# Minimal_carrier_board_for_CM4_rev_E.net
KiCad netlist of a schematic drawn in EAGLE
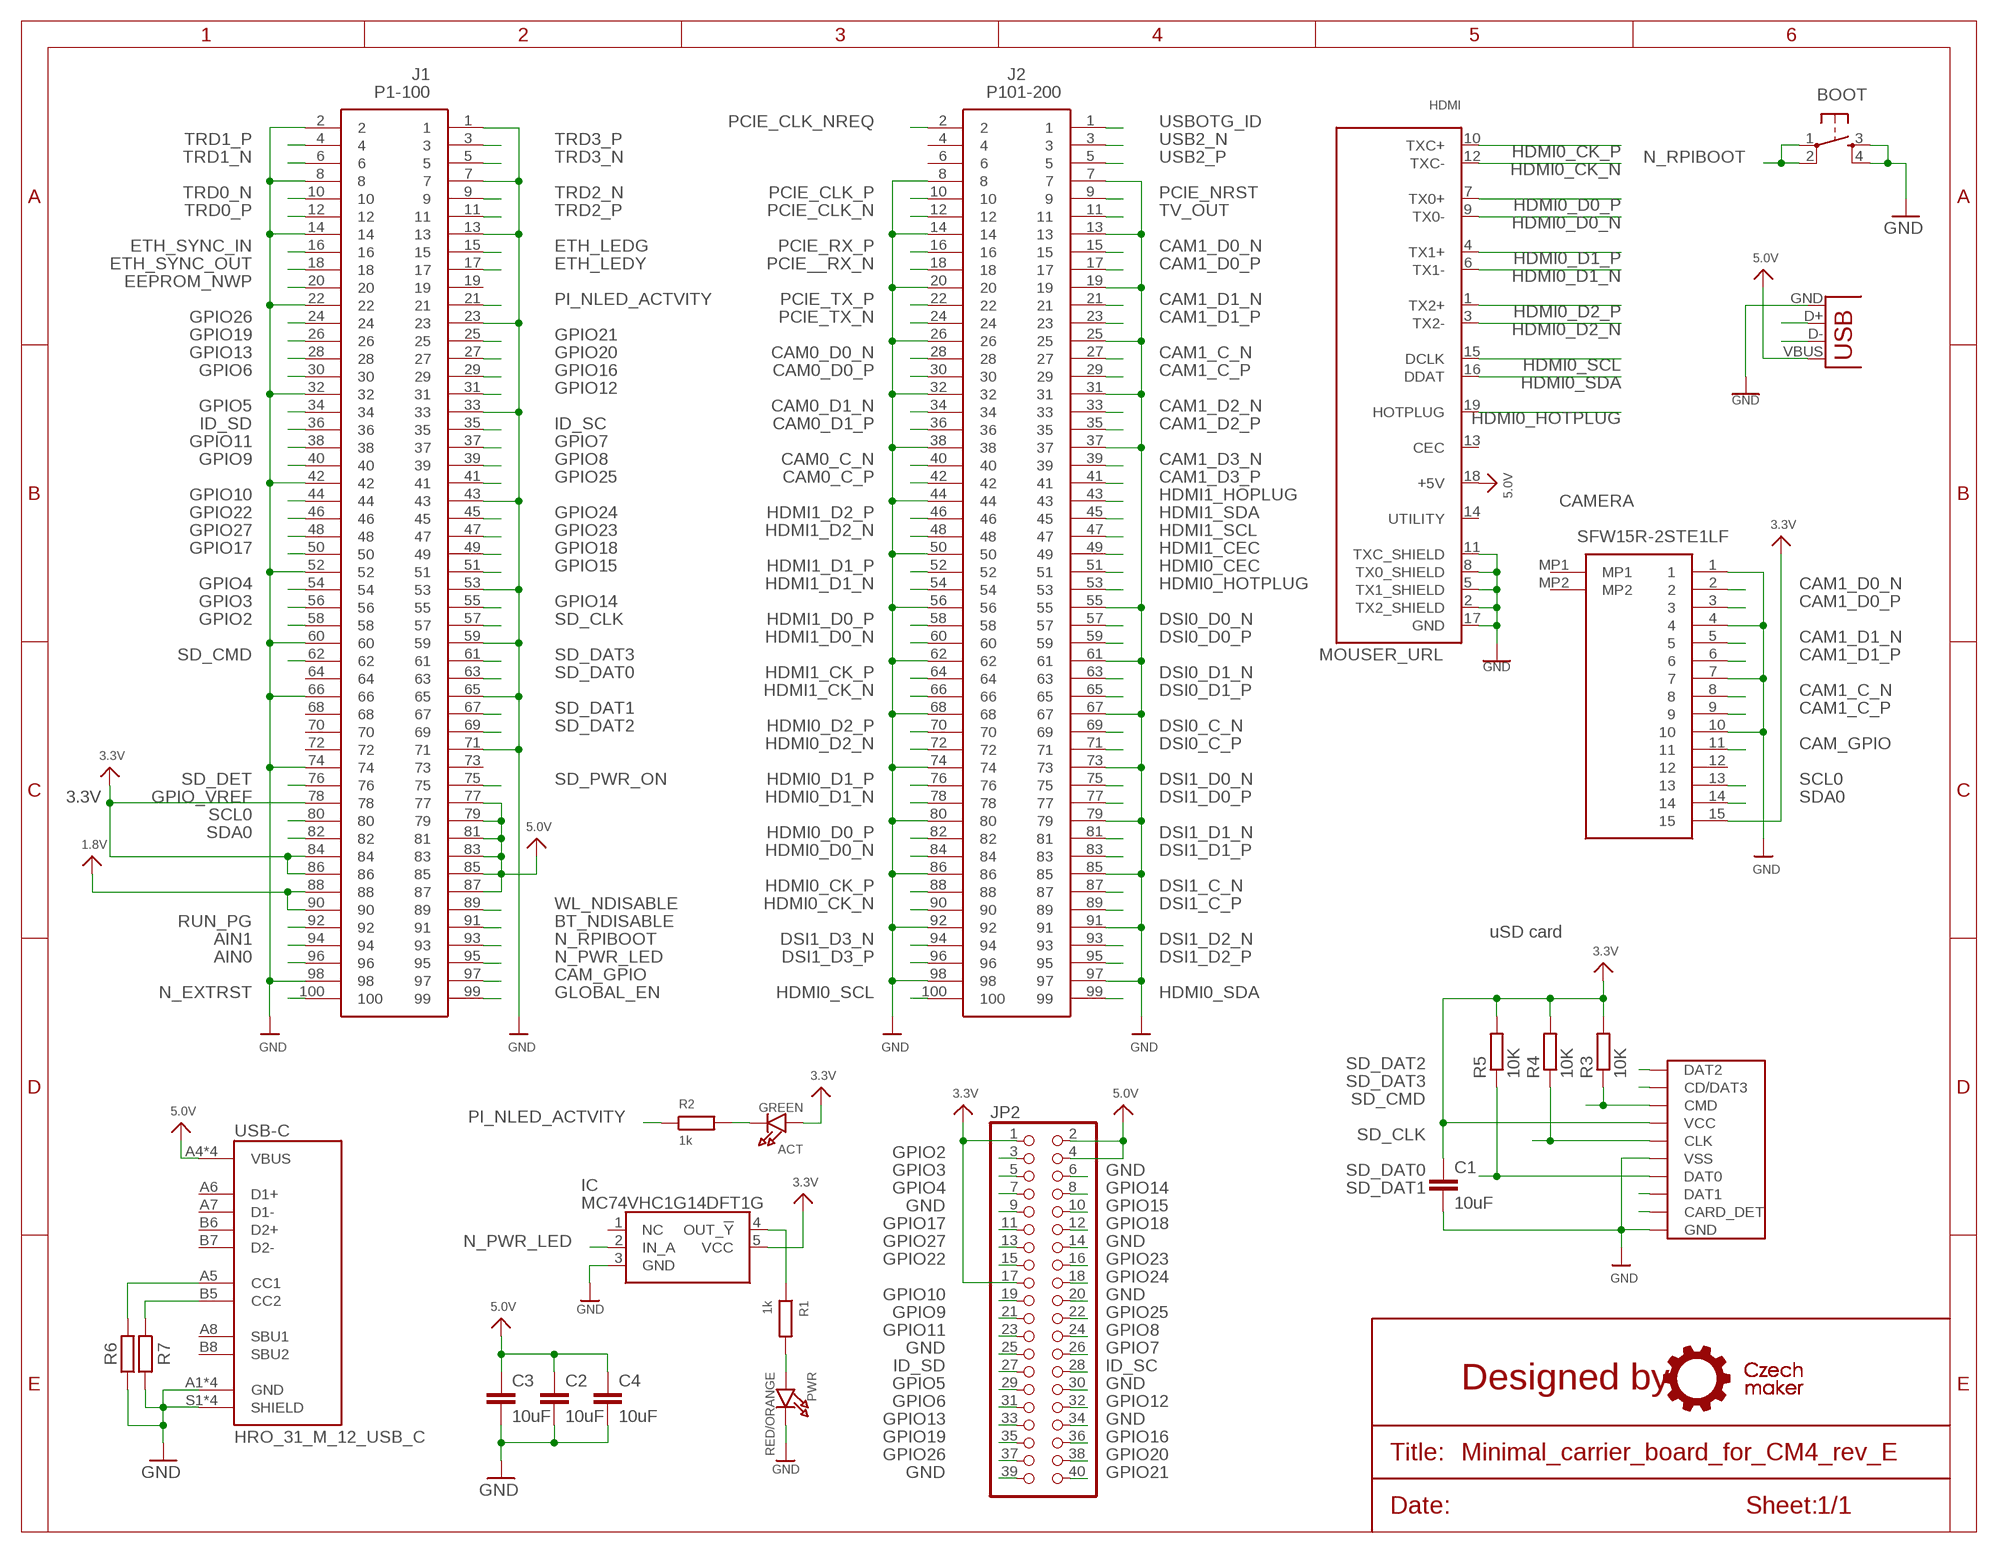
[diagram p0: schematic, sheet 1]

(export (version "E")
  (design (tool "Eeschema 10.0.6"))
  (components
    (comp (ref "ACT")
      (value "GREEN")
      (footprint "eagle-import:CHIPLED_0805_NOOUTLINE")
      (libsource (lib "eagle-import") (part "LED0805_NOOUTLINE"))
    )
    (comp (ref "BOOT")
      (value "TACTILE_SWITCHE_5X5_MICRO_")
      (footprint "eagle-import:TACTILE_SWITCH_5X5_MICRO")
      (libsource (lib "eagle-import") (part "TACTILE_SWITCHE_5X5_MICRO_"))
    )
    (comp (ref "C1")
      (value "10uF")
      (footprint "eagle-import:C0805")
      (libsource (lib "eagle-import") (part "C-EUC0805"))
    )
    (comp (ref "C2")
      (value "10uF")
      (footprint "eagle-import:C0805")
      (libsource (lib "eagle-import") (part "C-EUC0805"))
    )
    (comp (ref "C3")
      (value "10uF")
      (footprint "eagle-import:C0805")
      (libsource (lib "eagle-import") (part "C-EUC0805"))
    )
    (comp (ref "C4")
      (value "10uF")
      (footprint "eagle-import:C0805")
      (libsource (lib "eagle-import") (part "C-EUC0805"))
    )
    (comp (ref "CAMERA")
      (value "SFW15R-2STE1LF")
      (footprint "eagle-import:SFW15R2STE1LF")
      (fields (field (name "MOUSER_PART_NUMBER") "649-SFW15R-2STE1LF"))
      (libsource (lib "eagle-import") (part "SFW15R-2STE1LF"))
    )
    (comp (ref "HDMI")
      (value "HDMI_MOLEX_47151-0001")
      (footprint "eagle-import:HDMI_MOLEX_47151-0001")
      (libsource (lib "eagle-import") (part "HDMI_MOLEX_47151-0001"))
    )
    (comp (ref "IC")
      (value "MC74VHC1G14DFT1G")
      (footprint "eagle-import:SOT65P210X110-5N")
      (fields (field (name "MOUSER_PART_NUMBER") "863-MC74VHC1G14DFT1G"))
      (libsource (lib "eagle-import") (part "MC74VHC1G14DFT1G"))
    )
    (comp (ref "J1")
      (value "P1-100")
      (footprint "eagle-import:DF40C100DS04V51")
      (fields
        (field (name "MANUFACTURER_PART_NUMBER") "DF40C-100DS-0.4V(51)")
        (field (name "MOUSER_PART_NUMBER") "798-DF40C100DS0.4V51")
      )
      (libsource (lib "eagle-import") (part "DF40C-100DS-0.4V_51_"))
    )
    (comp (ref "J2")
      (value "P101-200")
      (footprint "eagle-import:DF40C100DS04V51")
      (fields
        (field (name "MANUFACTURER_PART_NUMBER") "DF40C-100DS-0.4V(51)")
        (field (name "MOUSER_PART_NUMBER") "798-DF40C100DS0.4V51")
      )
      (libsource (lib "eagle-import") (part "DF40C-100DS-0.4V_51_"))
    )
    (comp (ref "JP2")
      (value "PINHD-2X20")
      (footprint "eagle-import:2X20")
      (libsource (lib "eagle-import") (part "PINHD-2X20"))
    )
    (comp (ref "PWR")
      (value "RED/ORANGE")
      (footprint "eagle-import:CHIPLED_0805_NOOUTLINE")
      (libsource (lib "eagle-import") (part "LED0805_NOOUTLINE"))
    )
    (comp (ref "R1")
      (value "1k")
      (footprint "eagle-import:R0805")
      (libsource (lib "eagle-import") (part "R-EU_R0805"))
    )
    (comp (ref "R2")
      (value "1k")
      (footprint "eagle-import:R0805")
      (libsource (lib "eagle-import") (part "R-EU_R0805"))
    )
    (comp (ref "R3")
      (value "10K")
      (footprint "eagle-import:R0805")
      (libsource (lib "eagle-import") (part "R-EU_R0805"))
    )
    (comp (ref "R4")
      (value "10K")
      (footprint "eagle-import:R0805")
      (libsource (lib "eagle-import") (part "R-EU_R0805"))
    )
    (comp (ref "R5")
      (value "10K")
      (footprint "eagle-import:R0805")
      (libsource (lib "eagle-import") (part "R-EU_R0805"))
    )
    (comp (ref "R6")
      (value "5.1k")
      (footprint "eagle-import:R0805")
      (libsource (lib "eagle-import") (part "R-EU_R0805"))
    )
    (comp (ref "R7")
      (value "5.1k")
      (footprint "eagle-import:R0805")
      (libsource (lib "eagle-import") (part "R-EU_R0805"))
    )
    (comp (ref "SD_CARD")
      (value "MICRO_SD_CARD_")
      (footprint "eagle-import:TFP09-2--12B")
      (libsource (lib "eagle-import") (part "MICRO_SD_CARD_"))
    )
    (comp (ref "USB-A")
      (value "USBA-PTH")
      (footprint "eagle-import:USB-A-F-PTH")
      (libsource (lib "eagle-import") (part "USBA-PTH"))
    )
    (comp (ref "USB-C")
      (value "HRO_31_M_12_USB_C")
      (footprint "eagle-import:HRO_31_M_12_USB_C")
      (libsource (lib "eagle-import") (part "HRO_31_M_12_USB_C"))
    )
  )
  (nets
    (net (code "1") (name "/AIN0") (class "Default")
      (node (ref "J1") (pin "96") (pinfunction "96_96") (pintype "bidirectional"))
    )
    (net (code "2") (name "/AIN1") (class "Default")
      (node (ref "J1") (pin "94") (pinfunction "94_94") (pintype "bidirectional"))
    )
    (net (code "3") (name "/BT_NDISABLE") (class "Default")
      (node (ref "J1") (pin "91") (pinfunction "91_91") (pintype "bidirectional"))
    )
    (net (code "4") (name "/CAM0_C_N") (class "Default")
      (node (ref "J2") (pin "40") (pinfunction "40_40") (pintype "bidirectional"))
    )
    (net (code "5") (name "/CAM0_C_P") (class "Default")
      (node (ref "J2") (pin "42") (pinfunction "42_42") (pintype "bidirectional"))
    )
    (net (code "6") (name "/CAM0_D0_N") (class "Default")
      (node (ref "J2") (pin "28") (pinfunction "28_28") (pintype "bidirectional"))
    )
    (net (code "7") (name "/CAM0_D0_P") (class "Default")
      (node (ref "J2") (pin "30") (pinfunction "30_30") (pintype "bidirectional"))
    )
    (net (code "8") (name "/CAM0_D1_N") (class "Default")
      (node (ref "J2") (pin "34") (pinfunction "34_34") (pintype "bidirectional"))
    )
    (net (code "9") (name "/CAM0_D1_P") (class "Default")
      (node (ref "J2") (pin "36") (pinfunction "36_36") (pintype "bidirectional"))
    )
    (net (code "10") (name "/CAM1_C_N") (class "Default")
      (node (ref "CAMERA") (pin "8") (pinfunction "8_8") (pintype "bidirectional"))
      (node (ref "J2") (pin "27") (pinfunction "27_27") (pintype "bidirectional"))
    )
    (net (code "11") (name "/CAM1_C_P") (class "Default")
      (node (ref "CAMERA") (pin "9") (pinfunction "9_9") (pintype "bidirectional"))
      (node (ref "J2") (pin "29") (pinfunction "29_29") (pintype "bidirectional"))
    )
    (net (code "12") (name "/CAM1_D0_N") (class "Default")
      (node (ref "CAMERA") (pin "2") (pinfunction "2_2") (pintype "bidirectional"))
      (node (ref "J2") (pin "15") (pinfunction "15_15") (pintype "bidirectional"))
    )
    (net (code "13") (name "/CAM1_D0_P") (class "Default")
      (node (ref "CAMERA") (pin "3") (pinfunction "3_3") (pintype "bidirectional"))
      (node (ref "J2") (pin "17") (pinfunction "17_17") (pintype "bidirectional"))
    )
    (net (code "14") (name "/CAM1_D1_N") (class "Default")
      (node (ref "CAMERA") (pin "5") (pinfunction "5_5") (pintype "bidirectional"))
      (node (ref "J2") (pin "21") (pinfunction "21_21") (pintype "bidirectional"))
    )
    (net (code "15") (name "/CAM1_D1_P") (class "Default")
      (node (ref "CAMERA") (pin "6") (pinfunction "6_6") (pintype "bidirectional"))
      (node (ref "J2") (pin "23") (pinfunction "23_23") (pintype "bidirectional"))
    )
    (net (code "16") (name "/CAM1_D2_N") (class "Default")
      (node (ref "J2") (pin "33") (pinfunction "33_33") (pintype "bidirectional"))
    )
    (net (code "17") (name "/CAM1_D2_P") (class "Default")
      (node (ref "J2") (pin "35") (pinfunction "35_35") (pintype "bidirectional"))
    )
    (net (code "18") (name "/CAM1_D3_N") (class "Default")
      (node (ref "J2") (pin "39") (pinfunction "39_39") (pintype "bidirectional"))
    )
    (net (code "19") (name "/CAM1_D3_P") (class "Default")
      (node (ref "J2") (pin "41") (pinfunction "41_41") (pintype "bidirectional"))
    )
    (net (code "20") (name "/CAM_GPIO") (class "Default")
      (node (ref "CAMERA") (pin "11") (pinfunction "11_11") (pintype "bidirectional"))
      (node (ref "J1") (pin "97") (pinfunction "97_97") (pintype "bidirectional"))
    )
    (net (code "21") (name "/DSI0_C_N") (class "Default")
      (node (ref "J2") (pin "69") (pinfunction "69_69") (pintype "bidirectional"))
    )
    (net (code "22") (name "/DSI0_C_P") (class "Default")
      (node (ref "J2") (pin "71") (pinfunction "71_71") (pintype "bidirectional"))
    )
    (net (code "23") (name "/DSI0_D0_N") (class "Default")
      (node (ref "J2") (pin "57") (pinfunction "57_57") (pintype "bidirectional"))
    )
    (net (code "24") (name "/DSI0_D0_P") (class "Default")
      (node (ref "J2") (pin "59") (pinfunction "59_59") (pintype "bidirectional"))
    )
    (net (code "25") (name "/DSI0_D1_N") (class "Default")
      (node (ref "J2") (pin "63") (pinfunction "63_63") (pintype "bidirectional"))
    )
    (net (code "26") (name "/DSI0_D1_P") (class "Default")
      (node (ref "J2") (pin "65") (pinfunction "65_65") (pintype "bidirectional"))
    )
    (net (code "27") (name "/DSI1_C_N") (class "Default")
      (node (ref "J2") (pin "87") (pinfunction "87_87") (pintype "bidirectional"))
    )
    (net (code "28") (name "/DSI1_C_P") (class "Default")
      (node (ref "J2") (pin "89") (pinfunction "89_89") (pintype "bidirectional"))
    )
    (net (code "29") (name "/DSI1_D0_N") (class "Default")
      (node (ref "J2") (pin "75") (pinfunction "75_75") (pintype "bidirectional"))
    )
    (net (code "30") (name "/DSI1_D0_P") (class "Default")
      (node (ref "J2") (pin "77") (pinfunction "77_77") (pintype "bidirectional"))
    )
    (net (code "31") (name "/DSI1_D1_N") (class "Default")
      (node (ref "J2") (pin "81") (pinfunction "81_81") (pintype "bidirectional"))
    )
    (net (code "32") (name "/DSI1_D1_P") (class "Default")
      (node (ref "J2") (pin "83") (pinfunction "83_83") (pintype "bidirectional"))
    )
    (net (code "33") (name "/DSI1_D2_N") (class "Default")
      (node (ref "J2") (pin "93") (pinfunction "93_93") (pintype "bidirectional"))
    )
    (net (code "34") (name "/DSI1_D2_P") (class "Default")
      (node (ref "J2") (pin "95") (pinfunction "95_95") (pintype "bidirectional"))
    )
    (net (code "35") (name "/DSI1_D3_N") (class "Default")
      (node (ref "J2") (pin "94") (pinfunction "94_94") (pintype "bidirectional"))
    )
    (net (code "36") (name "/DSI1_D3_P") (class "Default")
      (node (ref "J2") (pin "96") (pinfunction "96_96") (pintype "bidirectional"))
    )
    (net (code "37") (name "/EEPROM_NWP") (class "Default")
      (node (ref "J1") (pin "20") (pinfunction "20_20") (pintype "bidirectional"))
    )
    (net (code "38") (name "/ETH_LEDG") (class "Default")
      (node (ref "J1") (pin "15") (pinfunction "15_15") (pintype "bidirectional"))
    )
    (net (code "39") (name "/ETH_LEDY") (class "Default")
      (node (ref "J1") (pin "17") (pinfunction "17_17") (pintype "bidirectional"))
    )
    (net (code "40") (name "/ETH_SYNC_IN") (class "Default")
      (node (ref "J1") (pin "16") (pinfunction "16_16") (pintype "bidirectional"))
    )
    (net (code "41") (name "/ETH_SYNC_OUT") (class "Default")
      (node (ref "J1") (pin "18") (pinfunction "18_18") (pintype "bidirectional"))
    )
    (net (code "42") (name "/GLOBAL_EN") (class "Default")
      (node (ref "J1") (pin "99") (pinfunction "99_99") (pintype "bidirectional"))
    )
    (net (code "43") (name "/GPIO2") (class "Default")
      (node (ref "J1") (pin "58") (pinfunction "58_58") (pintype "bidirectional"))
      (node (ref "JP2") (pin "3") (pinfunction "3_3") (pintype "passive"))
    )
    (net (code "44") (name "/GPIO3") (class "Default")
      (node (ref "J1") (pin "56") (pinfunction "56_56") (pintype "bidirectional"))
      (node (ref "JP2") (pin "5") (pinfunction "5_5") (pintype "passive"))
    )
    (net (code "45") (name "/GPIO4") (class "Default")
      (node (ref "J1") (pin "54") (pinfunction "54_54") (pintype "bidirectional"))
      (node (ref "JP2") (pin "7") (pinfunction "7_7") (pintype "passive"))
    )
    (net (code "46") (name "/GPIO5") (class "Default")
      (node (ref "J1") (pin "34") (pinfunction "34_34") (pintype "bidirectional"))
      (node (ref "JP2") (pin "29") (pinfunction "29_29") (pintype "passive"))
    )
    (net (code "47") (name "/GPIO6") (class "Default")
      (node (ref "J1") (pin "30") (pinfunction "30_30") (pintype "bidirectional"))
      (node (ref "JP2") (pin "31") (pinfunction "31_31") (pintype "passive"))
    )
    (net (code "48") (name "/GPIO7") (class "Default")
      (node (ref "J1") (pin "37") (pinfunction "37_37") (pintype "bidirectional"))
      (node (ref "JP2") (pin "26") (pinfunction "26_26") (pintype "passive"))
    )
    (net (code "49") (name "/GPIO8") (class "Default")
      (node (ref "J1") (pin "39") (pinfunction "39_39") (pintype "bidirectional"))
      (node (ref "JP2") (pin "24") (pinfunction "24_24") (pintype "passive"))
    )
    (net (code "50") (name "/GPIO9") (class "Default")
      (node (ref "J1") (pin "40") (pinfunction "40_40") (pintype "bidirectional"))
      (node (ref "JP2") (pin "21") (pinfunction "21_21") (pintype "passive"))
    )
    (net (code "51") (name "/GPIO10") (class "Default")
      (node (ref "J1") (pin "44") (pinfunction "44_44") (pintype "bidirectional"))
      (node (ref "JP2") (pin "19") (pinfunction "19_19") (pintype "passive"))
    )
    (net (code "52") (name "/GPIO11") (class "Default")
      (node (ref "J1") (pin "38") (pinfunction "38_38") (pintype "bidirectional"))
      (node (ref "JP2") (pin "23") (pinfunction "23_23") (pintype "passive"))
    )
    (net (code "53") (name "/GPIO12") (class "Default")
      (node (ref "J1") (pin "31") (pinfunction "31_31") (pintype "bidirectional"))
      (node (ref "JP2") (pin "32") (pinfunction "32_32") (pintype "passive"))
    )
    (net (code "54") (name "/GPIO13") (class "Default")
      (node (ref "J1") (pin "28") (pinfunction "28_28") (pintype "bidirectional"))
      (node (ref "JP2") (pin "33") (pinfunction "33_33") (pintype "passive"))
    )
    (net (code "55") (name "/GPIO14") (class "Default")
      (node (ref "J1") (pin "55") (pinfunction "55_55") (pintype "bidirectional"))
      (node (ref "JP2") (pin "8") (pinfunction "8_8") (pintype "passive"))
    )
    (net (code "56") (name "/GPIO15") (class "Default")
      (node (ref "J1") (pin "51") (pinfunction "51_51") (pintype "bidirectional"))
      (node (ref "JP2") (pin "10") (pinfunction "10_10") (pintype "passive"))
    )
    (net (code "57") (name "/GPIO16") (class "Default")
      (node (ref "J1") (pin "29") (pinfunction "29_29") (pintype "bidirectional"))
      (node (ref "JP2") (pin "36") (pinfunction "36_36") (pintype "passive"))
    )
    (net (code "58") (name "/GPIO17") (class "Default")
      (node (ref "J1") (pin "50") (pinfunction "50_50") (pintype "bidirectional"))
      (node (ref "JP2") (pin "11") (pinfunction "11_11") (pintype "passive"))
    )
    (net (code "59") (name "/GPIO18") (class "Default")
      (node (ref "J1") (pin "49") (pinfunction "49_49") (pintype "bidirectional"))
      (node (ref "JP2") (pin "12") (pinfunction "12_12") (pintype "passive"))
    )
    (net (code "60") (name "/GPIO19") (class "Default")
      (node (ref "J1") (pin "26") (pinfunction "26_26") (pintype "bidirectional"))
      (node (ref "JP2") (pin "35") (pinfunction "35_35") (pintype "passive"))
    )
    (net (code "61") (name "/GPIO20") (class "Default")
      (node (ref "J1") (pin "27") (pinfunction "27_27") (pintype "bidirectional"))
      (node (ref "JP2") (pin "38") (pinfunction "38_38") (pintype "passive"))
    )
    (net (code "62") (name "/GPIO21") (class "Default")
      (node (ref "J1") (pin "25") (pinfunction "25_25") (pintype "bidirectional"))
      (node (ref "JP2") (pin "40") (pinfunction "40_40") (pintype "passive"))
    )
    (net (code "63") (name "/GPIO22") (class "Default")
      (node (ref "J1") (pin "46") (pinfunction "46_46") (pintype "bidirectional"))
      (node (ref "JP2") (pin "15") (pinfunction "15_15") (pintype "passive"))
    )
    (net (code "64") (name "/GPIO23") (class "Default")
      (node (ref "J1") (pin "47") (pinfunction "47_47") (pintype "bidirectional"))
      (node (ref "JP2") (pin "16") (pinfunction "16_16") (pintype "passive"))
    )
    (net (code "65") (name "/GPIO24") (class "Default")
      (node (ref "J1") (pin "45") (pinfunction "45_45") (pintype "bidirectional"))
      (node (ref "JP2") (pin "18") (pinfunction "18_18") (pintype "passive"))
    )
    (net (code "66") (name "/GPIO25") (class "Default")
      (node (ref "J1") (pin "41") (pinfunction "41_41") (pintype "bidirectional"))
      (node (ref "JP2") (pin "22") (pinfunction "22_22") (pintype "passive"))
    )
    (net (code "67") (name "/GPIO26") (class "Default")
      (node (ref "J1") (pin "24") (pinfunction "24_24") (pintype "bidirectional"))
      (node (ref "JP2") (pin "37") (pinfunction "37_37") (pintype "passive"))
    )
    (net (code "68") (name "/GPIO27") (class "Default")
      (node (ref "J1") (pin "48") (pinfunction "48_48") (pintype "bidirectional"))
      (node (ref "JP2") (pin "13") (pinfunction "13_13") (pintype "passive"))
    )
    (net (code "69") (name "/HDMI0_CEC") (class "Default")
      (node (ref "J2") (pin "51") (pinfunction "51_51") (pintype "bidirectional"))
    )
    (net (code "70") (name "/HDMI0_CK_N") (class "Default")
      (node (ref "HDMI") (pin "12") (pinfunction "TXC-_12") (pintype "bidirectional"))
      (node (ref "J2") (pin "90") (pinfunction "90_90") (pintype "bidirectional"))
    )
    (net (code "71") (name "/HDMI0_CK_P") (class "Default")
      (node (ref "HDMI") (pin "10") (pinfunction "TXC+_10") (pintype "bidirectional"))
      (node (ref "J2") (pin "88") (pinfunction "88_88") (pintype "bidirectional"))
    )
    (net (code "72") (name "/HDMI0_D0_N") (class "Default")
      (node (ref "HDMI") (pin "9") (pinfunction "TX0-_9") (pintype "bidirectional"))
      (node (ref "J2") (pin "84") (pinfunction "84_84") (pintype "bidirectional"))
    )
    (net (code "73") (name "/HDMI0_D0_P") (class "Default")
      (node (ref "HDMI") (pin "7") (pinfunction "TX0+_7") (pintype "bidirectional"))
      (node (ref "J2") (pin "82") (pinfunction "82_82") (pintype "bidirectional"))
    )
    (net (code "74") (name "/HDMI0_D1_N") (class "Default")
      (node (ref "HDMI") (pin "6") (pinfunction "TX1-_6") (pintype "bidirectional"))
      (node (ref "J2") (pin "78") (pinfunction "78_78") (pintype "bidirectional"))
    )
    (net (code "75") (name "/HDMI0_D1_P") (class "Default")
      (node (ref "HDMI") (pin "4") (pinfunction "TX1+_4") (pintype "bidirectional"))
      (node (ref "J2") (pin "76") (pinfunction "76_76") (pintype "bidirectional"))
    )
    (net (code "76") (name "/HDMI0_D2_N") (class "Default")
      (node (ref "HDMI") (pin "3") (pinfunction "TX2-_3") (pintype "bidirectional"))
      (node (ref "J2") (pin "72") (pinfunction "72_72") (pintype "bidirectional"))
    )
    (net (code "77") (name "/HDMI0_D2_P") (class "Default")
      (node (ref "HDMI") (pin "1") (pinfunction "TX2+_1") (pintype "bidirectional"))
      (node (ref "J2") (pin "70") (pinfunction "70_70") (pintype "bidirectional"))
    )
    (net (code "78") (name "/HDMI0_HOTPLUG") (class "Default")
      (node (ref "HDMI") (pin "19") (pinfunction "HOTPLUG_19") (pintype "bidirectional"))
      (node (ref "J2") (pin "53") (pinfunction "53_53") (pintype "bidirectional"))
    )
    (net (code "79") (name "/HDMI0_SCL") (class "Default")
      (node (ref "HDMI") (pin "15") (pinfunction "DCLK_15") (pintype "bidirectional"))
      (node (ref "J2") (pin "100") (pinfunction "100_100") (pintype "bidirectional"))
    )
    (net (code "80") (name "/HDMI0_SDA") (class "Default")
      (node (ref "HDMI") (pin "16") (pinfunction "DDAT_16") (pintype "bidirectional"))
      (node (ref "J2") (pin "99") (pinfunction "99_99") (pintype "bidirectional"))
    )
    (net (code "81") (name "/HDMI1_CEC") (class "Default")
      (node (ref "J2") (pin "49") (pinfunction "49_49") (pintype "bidirectional"))
    )
    (net (code "82") (name "/HDMI1_CK_N") (class "Default")
      (node (ref "J2") (pin "66") (pinfunction "66_66") (pintype "bidirectional"))
    )
    (net (code "83") (name "/HDMI1_CK_P") (class "Default")
      (node (ref "J2") (pin "64") (pinfunction "64_64") (pintype "bidirectional"))
    )
    (net (code "84") (name "/HDMI1_D0_N") (class "Default")
      (node (ref "J2") (pin "60") (pinfunction "60_60") (pintype "bidirectional"))
    )
    (net (code "85") (name "/HDMI1_D0_P") (class "Default")
      (node (ref "J2") (pin "58") (pinfunction "58_58") (pintype "bidirectional"))
    )
    (net (code "86") (name "/HDMI1_D1_N") (class "Default")
      (node (ref "J2") (pin "54") (pinfunction "54_54") (pintype "bidirectional"))
    )
    (net (code "87") (name "/HDMI1_D1_P") (class "Default")
      (node (ref "J2") (pin "52") (pinfunction "52_52") (pintype "bidirectional"))
    )
    (net (code "88") (name "/HDMI1_D2_N") (class "Default")
      (node (ref "J2") (pin "48") (pinfunction "48_48") (pintype "bidirectional"))
    )
    (net (code "89") (name "/HDMI1_D2_P") (class "Default")
      (node (ref "J2") (pin "46") (pinfunction "46_46") (pintype "bidirectional"))
    )
    (net (code "90") (name "/HDMI1_HOPLUG") (class "Default")
      (node (ref "J2") (pin "43") (pinfunction "43_43") (pintype "bidirectional"))
    )
    (net (code "91") (name "/HDMI1_SCL") (class "Default")
      (node (ref "J2") (pin "47") (pinfunction "47_47") (pintype "bidirectional"))
    )
    (net (code "92") (name "/HDMI1_SDA") (class "Default")
      (node (ref "J2") (pin "45") (pinfunction "45_45") (pintype "bidirectional"))
    )
    (net (code "93") (name "/ID_SC") (class "Default")
      (node (ref "J1") (pin "35") (pinfunction "35_35") (pintype "bidirectional"))
      (node (ref "JP2") (pin "28") (pinfunction "28_28") (pintype "passive"))
    )
    (net (code "94") (name "/ID_SD") (class "Default")
      (node (ref "J1") (pin "36") (pinfunction "36_36") (pintype "bidirectional"))
      (node (ref "JP2") (pin "27") (pinfunction "27_27") (pintype "passive"))
    )
    (net (code "95") (name "/N_EXTRST") (class "Default")
      (node (ref "J1") (pin "100") (pinfunction "100_100") (pintype "bidirectional"))
    )
    (net (code "96") (name "/N_PWR_LED") (class "Default")
      (node (ref "IC") (pin "2") (pinfunction "IN_A_2") (pintype "input"))
      (node (ref "J1") (pin "95") (pinfunction "95_95") (pintype "bidirectional"))
    )
    (net (code "97") (name "/N_RPIBOOT") (class "Default")
      (node (ref "BOOT") (pin "1") (pinfunction "1_1") (pintype "passive"))
      (node (ref "BOOT") (pin "2") (pinfunction "2_2") (pintype "passive"))
      (node (ref "J1") (pin "93") (pinfunction "93_93") (pintype "bidirectional"))
    )
    (net (code "98") (name "/PCIE_CLK_N") (class "Default")
      (node (ref "J2") (pin "12") (pinfunction "12_12") (pintype "bidirectional"))
    )
    (net (code "99") (name "/PCIE_CLK_NREQ") (class "Default")
      (node (ref "J2") (pin "2") (pinfunction "2_2") (pintype "bidirectional"))
    )
    (net (code "100") (name "/PCIE_CLK_P") (class "Default")
      (node (ref "J2") (pin "10") (pinfunction "10_10") (pintype "bidirectional"))
    )
    (net (code "101") (name "/PCIE_NRST") (class "Default")
      (node (ref "J2") (pin "9") (pinfunction "9_9") (pintype "bidirectional"))
    )
    (net (code "102") (name "/PCIE_RX_P") (class "Default")
      (node (ref "J2") (pin "16") (pinfunction "16_16") (pintype "bidirectional"))
    )
    (net (code "103") (name "/PCIE_TX_N") (class "Default")
      (node (ref "J2") (pin "24") (pinfunction "24_24") (pintype "bidirectional"))
    )
    (net (code "104") (name "/PCIE_TX_P") (class "Default")
      (node (ref "J2") (pin "22") (pinfunction "22_22") (pintype "bidirectional"))
    )
    (net (code "105") (name "/PCIE__RX_N") (class "Default")
      (node (ref "J2") (pin "18") (pinfunction "18_18") (pintype "bidirectional"))
    )
    (net (code "106") (name "/PI_NLED_ACTVITY") (class "Default")
      (node (ref "J1") (pin "21") (pinfunction "21_21") (pintype "bidirectional"))
      (node (ref "R2") (pin "1") (pinfunction "1_1") (pintype "passive"))
    )
    (net (code "107") (name "/RUN_PG") (class "Default")
      (node (ref "J1") (pin "92") (pinfunction "92_92") (pintype "bidirectional"))
    )
    (net (code "108") (name "/SCL0") (class "Default")
      (node (ref "CAMERA") (pin "13") (pinfunction "13_13") (pintype "bidirectional"))
      (node (ref "J1") (pin "80") (pinfunction "80_80") (pintype "bidirectional"))
    )
    (net (code "109") (name "/SDA0") (class "Default")
      (node (ref "CAMERA") (pin "14") (pinfunction "14_14") (pintype "bidirectional"))
      (node (ref "J1") (pin "82") (pinfunction "82_82") (pintype "bidirectional"))
    )
    (net (code "110") (name "/SD_CLK") (class "Default")
      (node (ref "J1") (pin "57") (pinfunction "57_57") (pintype "bidirectional"))
      (node (ref "R4") (pin "1") (pinfunction "1_1") (pintype "passive"))
      (node (ref "SD_CARD") (pin "CLK") (pinfunction "CLK_CLK") (pintype "bidirectional"))
    )
    (net (code "111") (name "/SD_CMD") (class "Default")
      (node (ref "J1") (pin "62") (pinfunction "62_62") (pintype "bidirectional"))
      (node (ref "R3") (pin "1") (pinfunction "1_1") (pintype "passive"))
      (node (ref "SD_CARD") (pin "CMD") (pinfunction "CMD_CMD") (pintype "bidirectional"))
    )
    (net (code "112") (name "/SD_DAT0") (class "Default")
      (node (ref "J1") (pin "63") (pinfunction "63_63") (pintype "bidirectional"))
      (node (ref "R5") (pin "1") (pinfunction "1_1") (pintype "passive"))
      (node (ref "SD_CARD") (pin "DAT0") (pinfunction "DAT0_DAT0") (pintype "bidirectional"))
    )
    (net (code "113") (name "/SD_DAT1") (class "Default")
      (node (ref "J1") (pin "67") (pinfunction "67_67") (pintype "bidirectional"))
      (node (ref "SD_CARD") (pin "DAT1") (pinfunction "DAT1_DAT1") (pintype "bidirectional"))
    )
    (net (code "114") (name "/SD_DAT2") (class "Default")
      (node (ref "J1") (pin "69") (pinfunction "69_69") (pintype "bidirectional"))
      (node (ref "SD_CARD") (pin "DAT2") (pinfunction "DAT2_DAT2") (pintype "bidirectional"))
    )
    (net (code "115") (name "/SD_DAT3") (class "Default")
      (node (ref "J1") (pin "61") (pinfunction "61_61") (pintype "bidirectional"))
      (node (ref "SD_CARD") (pin "CD/DAT3") (pinfunction "CD/DAT3_CD/DAT3") (pintype "bidirectional"))
    )
    (net (code "116") (name "/SD_DET") (class "Default")
      (node (ref "J1") (pin "76") (pinfunction "76_76") (pintype "bidirectional"))
    )
    (net (code "117") (name "/SD_PWR_ON") (class "Default")
      (node (ref "J1") (pin "75") (pinfunction "75_75") (pintype "bidirectional"))
    )
    (net (code "118") (name "/TRD0_N") (class "Default")
      (node (ref "J1") (pin "10") (pinfunction "10_10") (pintype "bidirectional"))
    )
    (net (code "119") (name "/TRD0_P") (class "Default")
      (node (ref "J1") (pin "12") (pinfunction "12_12") (pintype "bidirectional"))
    )
    (net (code "120") (name "/TRD1_N") (class "Default")
      (node (ref "J1") (pin "6") (pinfunction "6_6") (pintype "bidirectional"))
    )
    (net (code "121") (name "/TRD1_P") (class "Default")
      (node (ref "J1") (pin "4") (pinfunction "4_4") (pintype "bidirectional"))
    )
    (net (code "122") (name "/TRD2_N") (class "Default")
      (node (ref "J1") (pin "9") (pinfunction "9_9") (pintype "bidirectional"))
    )
    (net (code "123") (name "/TRD2_P") (class "Default")
      (node (ref "J1") (pin "11") (pinfunction "11_11") (pintype "bidirectional"))
    )
    (net (code "124") (name "/TRD3_N") (class "Default")
      (node (ref "J1") (pin "5") (pinfunction "5_5") (pintype "bidirectional"))
    )
    (net (code "125") (name "/TRD3_P") (class "Default")
      (node (ref "J1") (pin "3") (pinfunction "3_3") (pintype "bidirectional"))
    )
    (net (code "126") (name "/TV_OUT") (class "Default")
      (node (ref "J2") (pin "11") (pinfunction "11_11") (pintype "bidirectional"))
    )
    (net (code "127") (name "/USB2_N") (class "Default")
      (node (ref "J2") (pin "3") (pinfunction "3_3") (pintype "bidirectional"))
      (node (ref "USB-A") (pin "D-") (pinfunction "D-_D-") (pintype "bidirectional"))
    )
    (net (code "128") (name "/USB2_P") (class "Default")
      (node (ref "J2") (pin "5") (pinfunction "5_5") (pintype "bidirectional"))
      (node (ref "USB-A") (pin "D+") (pinfunction "D+_D+") (pintype "bidirectional"))
    )
    (net (code "129") (name "/USBOTG_ID") (class "Default")
      (node (ref "J2") (pin "1") (pinfunction "1_1") (pintype "bidirectional"))
    )
    (net (code "130") (name "/WL_NDISABLE") (class "Default")
      (node (ref "J1") (pin "89") (pinfunction "89_89") (pintype "bidirectional"))
    )
    (net (code "131") (name "1.8V") (class "Default")
      (node (ref "J1") (pin "88") (pinfunction "88_88") (pintype "bidirectional"))
      (node (ref "J1") (pin "90") (pinfunction "90_90") (pintype "bidirectional"))
    )
    (net (code "132") (name "3.3V") (class "Default")
      (node (ref "ACT") (pin "A") (pinfunction "A_A") (pintype "passive"))
      (node (ref "C1") (pin "1") (pinfunction "1_1") (pintype "passive"))
      (node (ref "CAMERA") (pin "15") (pinfunction "15_15") (pintype "bidirectional"))
      (node (ref "IC") (pin "5") (pinfunction "VCC_5") (pintype "power_in"))
      (node (ref "J1") (pin "78") (pinfunction "78_78") (pintype "bidirectional"))
      (node (ref "J1") (pin "84") (pinfunction "84_84") (pintype "bidirectional"))
      (node (ref "J1") (pin "86") (pinfunction "86_86") (pintype "bidirectional"))
      (node (ref "JP2") (pin "1") (pinfunction "1_1") (pintype "passive"))
      (node (ref "JP2") (pin "17") (pinfunction "17_17") (pintype "passive"))
      (node (ref "R3") (pin "2") (pinfunction "2_2") (pintype "passive"))
      (node (ref "R4") (pin "2") (pinfunction "2_2") (pintype "passive"))
      (node (ref "R5") (pin "2") (pinfunction "2_2") (pintype "passive"))
      (node (ref "SD_CARD") (pin "VCC") (pinfunction "VCC_VCC") (pintype "bidirectional"))
    )
    (net (code "133") (name "5.0V") (class "Default")
      (node (ref "C2") (pin "1") (pinfunction "1_1") (pintype "passive"))
      (node (ref "C3") (pin "1") (pinfunction "1_1") (pintype "passive"))
      (node (ref "C4") (pin "1") (pinfunction "1_1") (pintype "passive"))
      (node (ref "HDMI") (pin "18") (pinfunction "+5V_18") (pintype "power_in"))
      (node (ref "J1") (pin "77") (pinfunction "77_77") (pintype "bidirectional"))
      (node (ref "J1") (pin "79") (pinfunction "79_79") (pintype "bidirectional"))
      (node (ref "J1") (pin "81") (pinfunction "81_81") (pintype "bidirectional"))
      (node (ref "J1") (pin "83") (pinfunction "83_83") (pintype "bidirectional"))
      (node (ref "J1") (pin "85") (pinfunction "85_85") (pintype "bidirectional"))
      (node (ref "J1") (pin "87") (pinfunction "87_87") (pintype "bidirectional"))
      (node (ref "JP2") (pin "2") (pinfunction "2_2") (pintype "passive"))
      (node (ref "JP2") (pin "4") (pinfunction "4_4") (pintype "passive"))
      (node (ref "USB-A") (pin "VBUS") (pinfunction "VBUS_VBUS") (pintype "bidirectional"))
      (node (ref "USB-C") (pin "A4") (pinfunction "VBUS_A4") (pintype "passive"))
      (node (ref "USB-C") (pin "A9") (pinfunction "VBUS_A9") (pintype "passive"))
      (node (ref "USB-C") (pin "B4") (pinfunction "VBUS_B4") (pintype "passive"))
      (node (ref "USB-C") (pin "B9") (pinfunction "VBUS_B9") (pintype "passive"))
    )
    (net (code "134") (name "GND") (class "Default")
      (node (ref "BOOT") (pin "3") (pinfunction "3_3") (pintype "passive"))
      (node (ref "BOOT") (pin "4") (pinfunction "4_4") (pintype "passive"))
      (node (ref "C1") (pin "2") (pinfunction "2_2") (pintype "passive"))
      (node (ref "C2") (pin "2") (pinfunction "2_2") (pintype "passive"))
      (node (ref "C3") (pin "2") (pinfunction "2_2") (pintype "passive"))
      (node (ref "C4") (pin "2") (pinfunction "2_2") (pintype "passive"))
      (node (ref "CAMERA") (pin "1") (pinfunction "1_1") (pintype "bidirectional"))
      (node (ref "CAMERA") (pin "10") (pinfunction "10_10") (pintype "bidirectional"))
      (node (ref "CAMERA") (pin "4") (pinfunction "4_4") (pintype "bidirectional"))
      (node (ref "CAMERA") (pin "7") (pinfunction "7_7") (pintype "bidirectional"))
      (node (ref "HDMI") (pin "11") (pinfunction "TXC_SHIELD_11") (pintype "power_in"))
      (node (ref "HDMI") (pin "17") (pinfunction "GND_17") (pintype "power_in"))
      (node (ref "HDMI") (pin "2") (pinfunction "TX2_SHIELD_2") (pintype "power_in"))
      (node (ref "HDMI") (pin "5") (pinfunction "TX1_SHIELD_5") (pintype "power_in"))
      (node (ref "HDMI") (pin "8") (pinfunction "TX0_SHIELD_8") (pintype "power_in"))
      (node (ref "IC") (pin "3") (pinfunction "GND_3") (pintype "power_in"))
      (node (ref "J1") (pin "1") (pinfunction "1_1") (pintype "bidirectional"))
      (node (ref "J1") (pin "13") (pinfunction "13_13") (pintype "bidirectional"))
      (node (ref "J1") (pin "14") (pinfunction "14_14") (pintype "bidirectional"))
      (node (ref "J1") (pin "2") (pinfunction "2_2") (pintype "bidirectional"))
      (node (ref "J1") (pin "22") (pinfunction "22_22") (pintype "bidirectional"))
      (node (ref "J1") (pin "23") (pinfunction "23_23") (pintype "bidirectional"))
      (node (ref "J1") (pin "32") (pinfunction "32_32") (pintype "bidirectional"))
      (node (ref "J1") (pin "33") (pinfunction "33_33") (pintype "bidirectional"))
      (node (ref "J1") (pin "42") (pinfunction "42_42") (pintype "bidirectional"))
      (node (ref "J1") (pin "43") (pinfunction "43_43") (pintype "bidirectional"))
      (node (ref "J1") (pin "52") (pinfunction "52_52") (pintype "bidirectional"))
      (node (ref "J1") (pin "53") (pinfunction "53_53") (pintype "bidirectional"))
      (node (ref "J1") (pin "59") (pinfunction "59_59") (pintype "bidirectional"))
      (node (ref "J1") (pin "60") (pinfunction "60_60") (pintype "bidirectional"))
      (node (ref "J1") (pin "65") (pinfunction "65_65") (pintype "bidirectional"))
      (node (ref "J1") (pin "66") (pinfunction "66_66") (pintype "bidirectional"))
      (node (ref "J1") (pin "7") (pinfunction "7_7") (pintype "bidirectional"))
      (node (ref "J1") (pin "71") (pinfunction "71_71") (pintype "bidirectional"))
      (node (ref "J1") (pin "74") (pinfunction "74_74") (pintype "bidirectional"))
      (node (ref "J1") (pin "8") (pinfunction "8_8") (pintype "bidirectional"))
      (node (ref "J1") (pin "98") (pinfunction "98_98") (pintype "bidirectional"))
      (node (ref "J2") (pin "13") (pinfunction "13_13") (pintype "bidirectional"))
      (node (ref "J2") (pin "14") (pinfunction "14_14") (pintype "bidirectional"))
      (node (ref "J2") (pin "19") (pinfunction "19_19") (pintype "bidirectional"))
      (node (ref "J2") (pin "20") (pinfunction "20_20") (pintype "bidirectional"))
      (node (ref "J2") (pin "25") (pinfunction "25_25") (pintype "bidirectional"))
      (node (ref "J2") (pin "26") (pinfunction "26_26") (pintype "bidirectional"))
      (node (ref "J2") (pin "31") (pinfunction "31_31") (pintype "bidirectional"))
      (node (ref "J2") (pin "32") (pinfunction "32_32") (pintype "bidirectional"))
      (node (ref "J2") (pin "37") (pinfunction "37_37") (pintype "bidirectional"))
      (node (ref "J2") (pin "38") (pinfunction "38_38") (pintype "bidirectional"))
      (node (ref "J2") (pin "44") (pinfunction "44_44") (pintype "bidirectional"))
      (node (ref "J2") (pin "50") (pinfunction "50_50") (pintype "bidirectional"))
      (node (ref "J2") (pin "55") (pinfunction "55_55") (pintype "bidirectional"))
      (node (ref "J2") (pin "56") (pinfunction "56_56") (pintype "bidirectional"))
      (node (ref "J2") (pin "61") (pinfunction "61_61") (pintype "bidirectional"))
      (node (ref "J2") (pin "62") (pinfunction "62_62") (pintype "bidirectional"))
      (node (ref "J2") (pin "67") (pinfunction "67_67") (pintype "bidirectional"))
      (node (ref "J2") (pin "68") (pinfunction "68_68") (pintype "bidirectional"))
      (node (ref "J2") (pin "7") (pinfunction "7_7") (pintype "bidirectional"))
      (node (ref "J2") (pin "73") (pinfunction "73_73") (pintype "bidirectional"))
      (node (ref "J2") (pin "74") (pinfunction "74_74") (pintype "bidirectional"))
      (node (ref "J2") (pin "79") (pinfunction "79_79") (pintype "bidirectional"))
      (node (ref "J2") (pin "8") (pinfunction "8_8") (pintype "bidirectional"))
      (node (ref "J2") (pin "80") (pinfunction "80_80") (pintype "bidirectional"))
      (node (ref "J2") (pin "85") (pinfunction "85_85") (pintype "bidirectional"))
      (node (ref "J2") (pin "86") (pinfunction "86_86") (pintype "bidirectional"))
      (node (ref "J2") (pin "91") (pinfunction "91_91") (pintype "bidirectional"))
      (node (ref "J2") (pin "92") (pinfunction "92_92") (pintype "bidirectional"))
      (node (ref "J2") (pin "97") (pinfunction "97_97") (pintype "bidirectional"))
      (node (ref "J2") (pin "98") (pinfunction "98_98") (pintype "bidirectional"))
      (node (ref "JP2") (pin "14") (pinfunction "14_14") (pintype "passive"))
      (node (ref "JP2") (pin "20") (pinfunction "20_20") (pintype "passive"))
      (node (ref "JP2") (pin "25") (pinfunction "25_25") (pintype "passive"))
      (node (ref "JP2") (pin "30") (pinfunction "30_30") (pintype "passive"))
      (node (ref "JP2") (pin "34") (pinfunction "34_34") (pintype "passive"))
      (node (ref "JP2") (pin "39") (pinfunction "39_39") (pintype "passive"))
      (node (ref "JP2") (pin "6") (pinfunction "6_6") (pintype "passive"))
      (node (ref "JP2") (pin "9") (pinfunction "9_9") (pintype "passive"))
      (node (ref "PWR") (pin "C") (pinfunction "C_C") (pintype "passive"))
      (node (ref "R6") (pin "1") (pinfunction "1_1") (pintype "passive"))
      (node (ref "R7") (pin "2") (pinfunction "2_2") (pintype "passive"))
      (node (ref "SD_CARD") (pin "GND") (pinfunction "GND_GND") (pintype "bidirectional"))
      (node (ref "SD_CARD") (pin "GND@1") (pinfunction "GND_GND@1") (pintype "bidirectional"))
      (node (ref "SD_CARD") (pin "GND@2") (pinfunction "GND_GND@2") (pintype "bidirectional"))
      (node (ref "SD_CARD") (pin "GND@3") (pinfunction "VSS_GND@3") (pintype "bidirectional"))
      (node (ref "SD_CARD") (pin "VSS") (pinfunction "GND_VSS") (pintype "bidirectional"))
      (node (ref "USB-A") (pin "GND") (pinfunction "GND_GND") (pintype "bidirectional"))
      (node (ref "USB-C") (pin "A1") (pinfunction "GND_A1") (pintype "passive"))
      (node (ref "USB-C") (pin "A12") (pinfunction "GND_A12") (pintype "passive"))
      (node (ref "USB-C") (pin "B1") (pinfunction "GND_B1") (pintype "passive"))
      (node (ref "USB-C") (pin "B12") (pinfunction "GND_B12") (pintype "passive"))
      (node (ref "USB-C") (pin "S1") (pinfunction "SHIELD_S1") (pintype "passive"))
      (node (ref "USB-C") (pin "S2") (pinfunction "SHIELD_S2") (pintype "passive"))
      (node (ref "USB-C") (pin "S3") (pinfunction "SHIELD_S3") (pintype "passive"))
      (node (ref "USB-C") (pin "S4") (pinfunction "SHIELD_S4") (pintype "passive"))
    )
    (net (code "135") (name "Net-(ACT-PadC)") (class "Default")
      (node (ref "ACT") (pin "C") (pinfunction "C_C") (pintype "passive"))
      (node (ref "R2") (pin "2") (pinfunction "2_2") (pintype "passive"))
    )
    (net (code "136") (name "Net-(IC-OUT_~{Y})") (class "Default")
      (node (ref "IC") (pin "4") (pinfunction "OUT_~{Y}_4") (pintype "output"))
      (node (ref "R1") (pin "1") (pinfunction "1_1") (pintype "passive"))
    )
    (net (code "137") (name "Net-(PWR-PadA)") (class "Default")
      (node (ref "PWR") (pin "A") (pinfunction "A_A") (pintype "passive"))
      (node (ref "R1") (pin "2") (pinfunction "2_2") (pintype "passive"))
    )
    (net (code "138") (name "Net-(USB-C-CC1)") (class "Default")
      (node (ref "R6") (pin "2") (pinfunction "2_2") (pintype "passive"))
      (node (ref "USB-C") (pin "A5") (pinfunction "CC1_A5") (pintype "passive"))
    )
    (net (code "139") (name "Net-(USB-C-CC2)") (class "Default")
      (node (ref "R7") (pin "1") (pinfunction "1_1") (pintype "passive"))
      (node (ref "USB-C") (pin "B5") (pinfunction "CC2_B5") (pintype "passive"))
    )
    (net (code "140") (name "unconnected-(CAMERA-Pad12)") (class "Default")
      (node (ref "CAMERA") (pin "12") (pinfunction "12_12") (pintype "bidirectional"))
    )
    (net (code "141") (name "unconnected-(CAMERA-PadMP1)") (class "Default")
      (node (ref "CAMERA") (pin "MP1") (pinfunction "MP1_MP1") (pintype "bidirectional"))
    )
    (net (code "142") (name "unconnected-(CAMERA-PadMP2)") (class "Default")
      (node (ref "CAMERA") (pin "MP2") (pinfunction "MP2_MP2") (pintype "bidirectional"))
    )
    (net (code "143") (name "unconnected-(HDMIA-CEC-Pad13)") (class "Default")
      (node (ref "HDMI") (pin "13") (pinfunction "CEC_13") (pintype "bidirectional"))
    )
    (net (code "144") (name "unconnected-(HDMIA-UTILITY-Pad14)") (class "Default")
      (node (ref "HDMI") (pin "14") (pinfunction "UTILITY_14") (pintype "bidirectional"))
    )
    (net (code "145") (name "unconnected-(IC-NC-Pad1)") (class "Default")
      (node (ref "IC") (pin "1") (pinfunction "NC_1") (pintype "no_connect"))
    )
    (net (code "146") (name "unconnected-(J1-Pad19)") (class "Default")
      (node (ref "J1") (pin "19") (pinfunction "19_19") (pintype "bidirectional"))
    )
    (net (code "147") (name "unconnected-(J1-Pad64)") (class "Default")
      (node (ref "J1") (pin "64") (pinfunction "64_64") (pintype "bidirectional"))
    )
    (net (code "148") (name "unconnected-(J1-Pad68)") (class "Default")
      (node (ref "J1") (pin "68") (pinfunction "68_68") (pintype "bidirectional"))
    )
    (net (code "149") (name "unconnected-(J1-Pad70)") (class "Default")
      (node (ref "J1") (pin "70") (pinfunction "70_70") (pintype "bidirectional"))
    )
    (net (code "150") (name "unconnected-(J1-Pad72)") (class "Default")
      (node (ref "J1") (pin "72") (pinfunction "72_72") (pintype "bidirectional"))
    )
    (net (code "151") (name "unconnected-(J1-Pad73)") (class "Default")
      (node (ref "J1") (pin "73") (pinfunction "73_73") (pintype "bidirectional"))
    )
    (net (code "152") (name "unconnected-(J2-Pad4)") (class "Default")
      (node (ref "J2") (pin "4") (pinfunction "4_4") (pintype "bidirectional"))
    )
    (net (code "153") (name "unconnected-(J2-Pad6)") (class "Default")
      (node (ref "J2") (pin "6") (pinfunction "6_6") (pintype "bidirectional"))
    )
    (net (code "154") (name "unconnected-(SD_CARD-CARD_DET-PadCD)") (class "Default")
      (node (ref "SD_CARD") (pin "CD") (pinfunction "CARD_DET_CD") (pintype "bidirectional"))
    )
    (net (code "155") (name "unconnected-(USB-C-D1+-PadA6)") (class "Default")
      (node (ref "USB-C") (pin "A6") (pinfunction "D1+_A6") (pintype "passive"))
    )
    (net (code "156") (name "unconnected-(USB-C-D1--PadA7)") (class "Default")
      (node (ref "USB-C") (pin "A7") (pinfunction "D1-_A7") (pintype "passive"))
    )
    (net (code "157") (name "unconnected-(USB-C-D2+-PadB6)") (class "Default")
      (node (ref "USB-C") (pin "B6") (pinfunction "D2+_B6") (pintype "passive"))
    )
    (net (code "158") (name "unconnected-(USB-C-D2--PadB7)") (class "Default")
      (node (ref "USB-C") (pin "B7") (pinfunction "D2-_B7") (pintype "passive"))
    )
    (net (code "159") (name "unconnected-(USB-C-SBU1-PadA8)") (class "Default")
      (node (ref "USB-C") (pin "A8") (pinfunction "SBU1_A8") (pintype "passive"))
    )
    (net (code "160") (name "unconnected-(USB-C-SBU2-PadB8)") (class "Default")
      (node (ref "USB-C") (pin "B8") (pinfunction "SBU2_B8") (pintype "passive"))
    )
  )
)
